# ESP-WROOM32-Breakout_v12.net
KiCad netlist of a schematic drawn in EAGLE
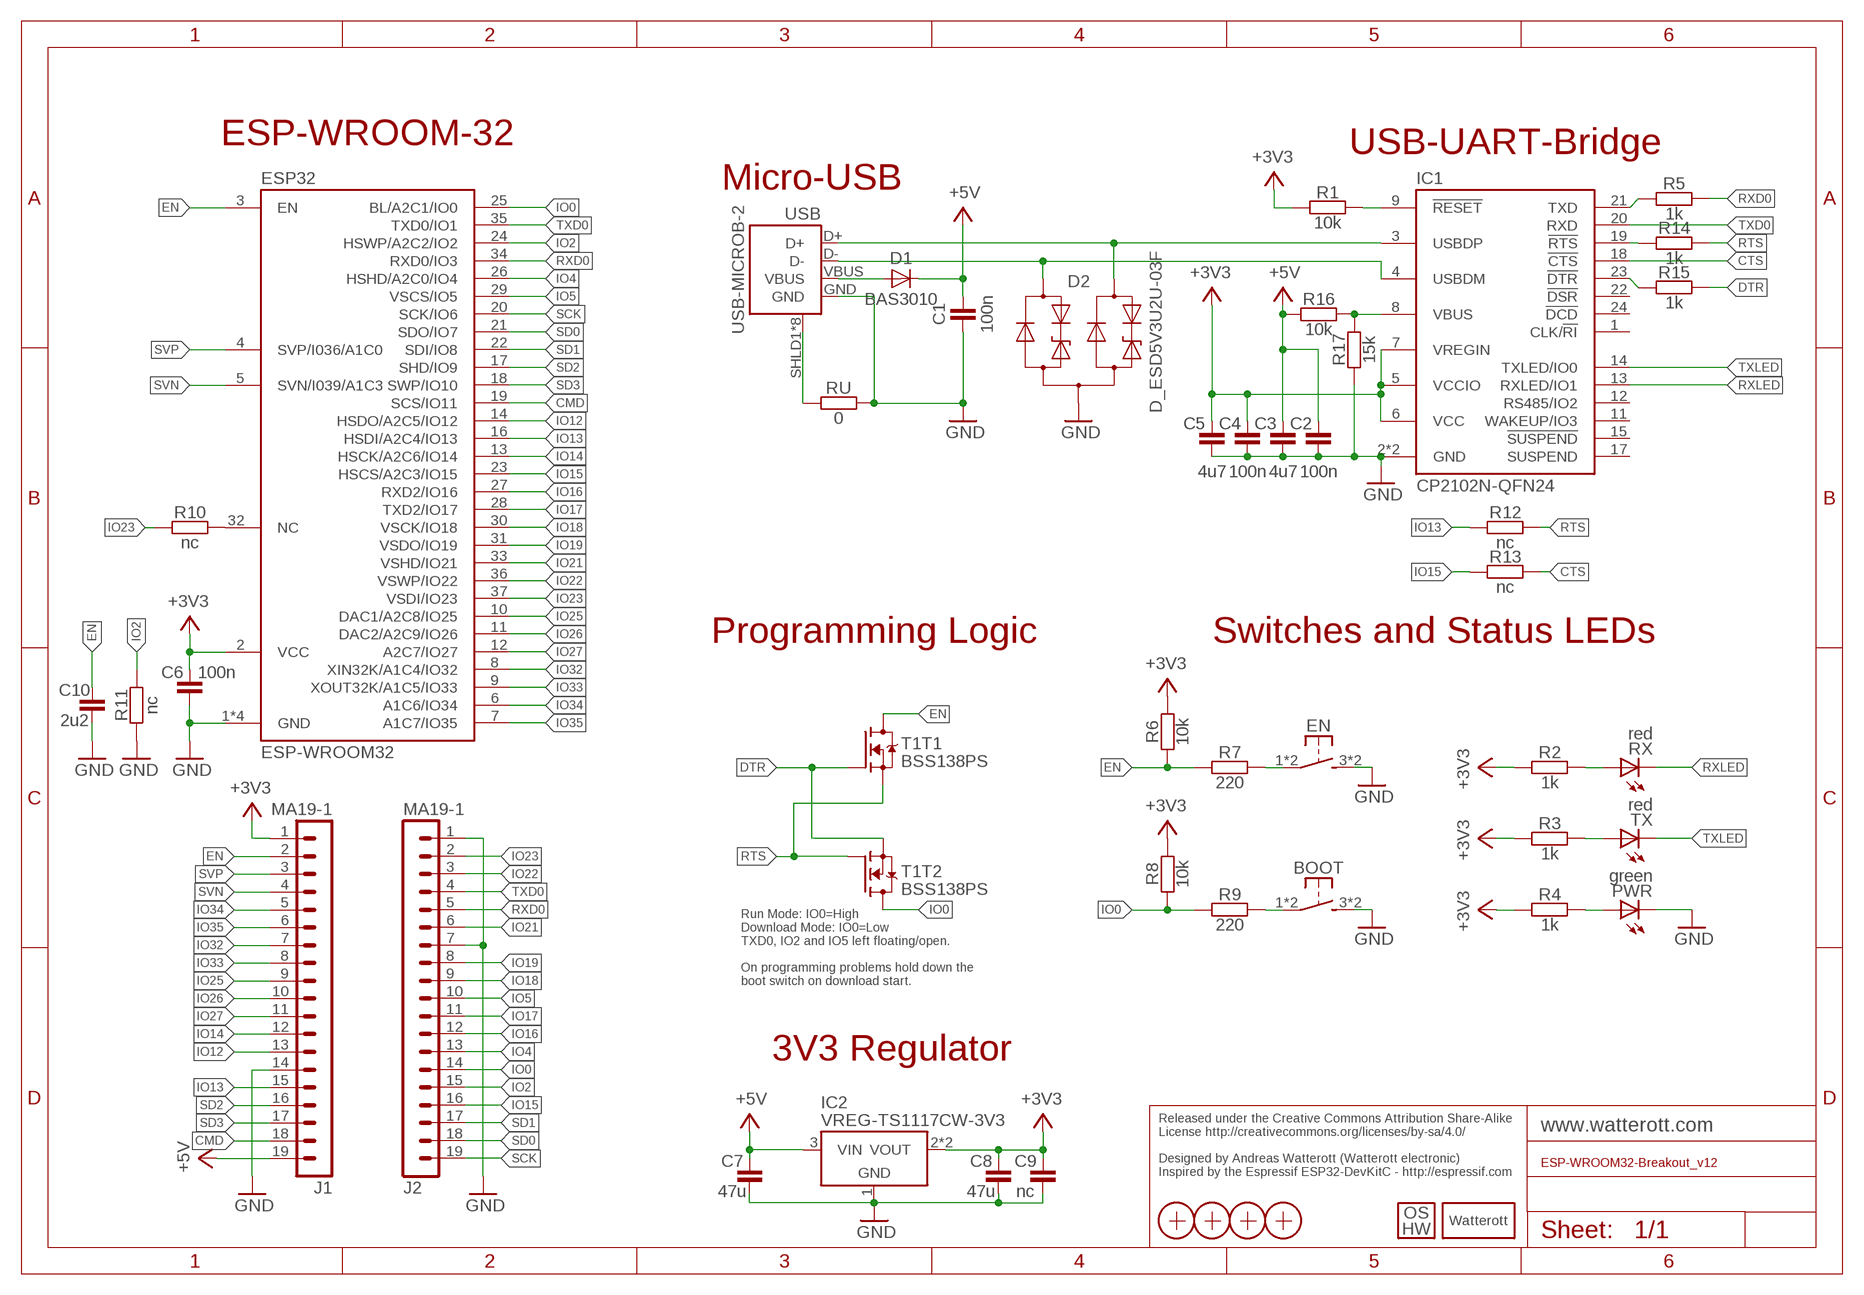
[diagram p0: schematic, sheet 1]

(export (version "E")
  (design (tool "Eeschema 10.0.6"))
  (components
    (comp (ref "BOOT")
      (value "SW-TACTILE-PTS840P")
      (footprint "eagle-import:PTS840P")
      (libsource (lib "eagle-import") (part "SW-TACTILE-PTS840P"))
    )
    (comp (ref "C1")
      (value "100n")
      (footprint "eagle-import:C0402")
      (libsource (lib "eagle-import") (part "CAPACITOR-0402"))
    )
    (comp (ref "C2")
      (value "100n")
      (footprint "eagle-import:C0402")
      (libsource (lib "eagle-import") (part "CAPACITOR-0402"))
    )
    (comp (ref "C3")
      (value "4u7")
      (footprint "eagle-import:C0603")
      (libsource (lib "eagle-import") (part "CAPACITOR-0603"))
    )
    (comp (ref "C4")
      (value "100n")
      (footprint "eagle-import:C0402")
      (libsource (lib "eagle-import") (part "CAPACITOR-0402"))
    )
    (comp (ref "C5")
      (value "4u7")
      (footprint "eagle-import:C0603")
      (libsource (lib "eagle-import") (part "CAPACITOR-0603"))
    )
    (comp (ref "C6")
      (value "100n")
      (footprint "eagle-import:C0402")
      (libsource (lib "eagle-import") (part "CAPACITOR-0402"))
    )
    (comp (ref "C7")
      (value "47u")
      (footprint "eagle-import:C1206")
      (libsource (lib "eagle-import") (part "CAPACITOR-1206"))
    )
    (comp (ref "C8")
      (value "47u")
      (footprint "eagle-import:C1206")
      (libsource (lib "eagle-import") (part "CAPACITOR-1206"))
    )
    (comp (ref "C9")
      (value "nc")
      (footprint "eagle-import:C1206")
      (libsource (lib "eagle-import") (part "CAPACITOR-1206"))
    )
    (comp (ref "C10")
      (value "2u2")
      (footprint "eagle-import:C0402")
      (libsource (lib "eagle-import") (part "CAPACITOR-0402"))
    )
    (comp (ref "D1")
      (value "BAS3010")
      (footprint "eagle-import:SOD323")
      (libsource (lib "eagle-import") (part "DIODE-SOD323"))
    )
    (comp (ref "D2")
      (value "D_ESD5V3U2U-03F")
      (footprint "eagle-import:SOT723")
      (libsource (lib "eagle-import") (part "D_ESD5V3U2U-03F"))
    )
    (comp (ref "EN")
      (value "SW-TACTILE-PTS840P")
      (footprint "eagle-import:PTS840P")
      (libsource (lib "eagle-import") (part "SW-TACTILE-PTS840P"))
    )
    (comp (ref "ESP32")
      (value "ESP-WROOM32")
      (footprint "eagle-import:ESP-WROOM32")
      (libsource (lib "eagle-import") (part "ESP-WROOM32"))
    )
    (comp (ref "IC1")
      (value "CP2102N-QFN24")
      (footprint "eagle-import:QFN24-PAD")
      (libsource (lib "eagle-import") (part "CP2102N-QFN24"))
    )
    (comp (ref "IC2")
      (value "VREG-TS1117CW-3V3")
      (footprint "eagle-import:SOT223")
      (libsource (lib "eagle-import") (part "VREG-TS1117CW-3V3"))
    )
    (comp (ref "J1")
      (value "MA19-1")
      (footprint "eagle-import:MA19-1")
      (libsource (lib "eagle-import") (part "MA19-1"))
    )
    (comp (ref "J2")
      (value "MA19-1")
      (footprint "eagle-import:MA19-1")
      (libsource (lib "eagle-import") (part "MA19-1"))
    )
    (comp (ref "LOGO1")
      (value "LOGO_SPARK-4")
      (footprint "eagle-import:SPARK_4MM")
      (libsource (lib "eagle-import") (part "LOGO_SPARK-4"))
    )
    (comp (ref "LOGO2")
      (value "LOGO_OSHW-2")
      (footprint "eagle-import:OSHW_2MM")
      (libsource (lib "eagle-import") (part "LOGO_OSHW-2"))
    )
    (comp (ref "PWR")
      (value "green")
      (footprint "eagle-import:C0603")
      (libsource (lib "eagle-import") (part "LED-0603"))
    )
    (comp (ref "R1")
      (value "10k")
      (footprint "eagle-import:C0402")
      (libsource (lib "eagle-import") (part "RESISTOR-0402"))
    )
    (comp (ref "R2")
      (value "1k")
      (footprint "eagle-import:C0402")
      (libsource (lib "eagle-import") (part "RESISTOR-0402"))
    )
    (comp (ref "R3")
      (value "1k")
      (footprint "eagle-import:C0402")
      (libsource (lib "eagle-import") (part "RESISTOR-0402"))
    )
    (comp (ref "R4")
      (value "1k")
      (footprint "eagle-import:C0402")
      (libsource (lib "eagle-import") (part "RESISTOR-0402"))
    )
    (comp (ref "R5")
      (value "1k")
      (footprint "eagle-import:C0402")
      (libsource (lib "eagle-import") (part "RESISTOR-0402"))
    )
    (comp (ref "R6")
      (value "10k")
      (footprint "eagle-import:C0402")
      (libsource (lib "eagle-import") (part "RESISTOR-0402"))
    )
    (comp (ref "R7")
      (value "220")
      (footprint "eagle-import:C0402")
      (libsource (lib "eagle-import") (part "RESISTOR-0402"))
    )
    (comp (ref "R8")
      (value "10k")
      (footprint "eagle-import:C0402")
      (libsource (lib "eagle-import") (part "RESISTOR-0402"))
    )
    (comp (ref "R9")
      (value "220")
      (footprint "eagle-import:C0402")
      (libsource (lib "eagle-import") (part "RESISTOR-0402"))
    )
    (comp (ref "R10")
      (value "nc")
      (footprint "eagle-import:C0402")
      (libsource (lib "eagle-import") (part "RESISTOR-0402"))
    )
    (comp (ref "R11")
      (value "nc")
      (footprint "eagle-import:C0402")
      (libsource (lib "eagle-import") (part "RESISTOR-0402"))
    )
    (comp (ref "R12")
      (value "nc")
      (footprint "eagle-import:C0402")
      (libsource (lib "eagle-import") (part "RESISTOR-0402"))
    )
    (comp (ref "R13")
      (value "nc")
      (footprint "eagle-import:C0402")
      (libsource (lib "eagle-import") (part "RESISTOR-0402"))
    )
    (comp (ref "R14")
      (value "1k")
      (footprint "eagle-import:C0402")
      (libsource (lib "eagle-import") (part "RESISTOR-0402"))
    )
    (comp (ref "R15")
      (value "1k")
      (footprint "eagle-import:C0402")
      (libsource (lib "eagle-import") (part "RESISTOR-0402"))
    )
    (comp (ref "R16")
      (value "10k")
      (footprint "eagle-import:C0402")
      (libsource (lib "eagle-import") (part "RESISTOR-0402"))
    )
    (comp (ref "R17")
      (value "15k")
      (footprint "eagle-import:C0402")
      (libsource (lib "eagle-import") (part "RESISTOR-0402"))
    )
    (comp (ref "RU")
      (value "0")
      (footprint "eagle-import:C0402")
      (libsource (lib "eagle-import") (part "RESISTOR-0402"))
    )
    (comp (ref "RX")
      (value "red")
      (footprint "eagle-import:C0603")
      (libsource (lib "eagle-import") (part "LED-0603"))
    )
    (comp (ref "T1")
      (value "BSS138PS")
      (footprint "eagle-import:SOT363")
      (libsource (lib "eagle-import") (part "BSS138PS"))
    )
    (comp (ref "TX")
      (value "red")
      (footprint "eagle-import:C0603")
      (libsource (lib "eagle-import") (part "LED-0603"))
    )
    (comp (ref "USB")
      (value "USB-MICROB-2")
      (footprint "eagle-import:USB-MICROB-10118194")
      (libsource (lib "eagle-import") (part "USB-MICROB-2"))
    )
    (comp (ref "X1")
      (value "PASSER-07")
      (footprint "eagle-import:PASSER_07MM")
      (libsource (lib "eagle-import") (part "PASSER-07"))
    )
    (comp (ref "X2")
      (value "PASSER-07")
      (footprint "eagle-import:PASSER_07MM")
      (libsource (lib "eagle-import") (part "PASSER-07"))
    )
    (comp (ref "X3")
      (value "PASSER-07")
      (footprint "eagle-import:PASSER_07MM")
      (libsource (lib "eagle-import") (part "PASSER-07"))
    )
    (comp (ref "X4")
      (value "PASSER-07")
      (footprint "eagle-import:PASSER_07MM")
      (libsource (lib "eagle-import") (part "PASSER-07"))
    )
  )
  (nets
    (net (code "1") (name "+3V3") (class "Default")
      (node (ref "C4") (pin "2") (pinfunction "2_2") (pintype "passive"))
      (node (ref "C5") (pin "2") (pinfunction "2_2") (pintype "passive"))
      (node (ref "C6") (pin "2") (pinfunction "2_2") (pintype "passive"))
      (node (ref "C8") (pin "2") (pinfunction "2_2") (pintype "passive"))
      (node (ref "C9") (pin "2") (pinfunction "2_2") (pintype "passive"))
      (node (ref "ESP32") (pin "2") (pinfunction "VCC_2") (pintype "power_in"))
      (node (ref "IC1") (pin "5") (pinfunction "VCCIO_5") (pintype "power_in"))
      (node (ref "IC1") (pin "6") (pinfunction "VCC_6") (pintype "power_in"))
      (node (ref "IC1") (pin "7") (pinfunction "VREGIN_7") (pintype "power_in"))
      (node (ref "IC2") (pin "2") (pinfunction "VOUT_2") (pintype "power_in"))
      (node (ref "IC2") (pin "4") (pinfunction "VOUT_4") (pintype "power_in"))
      (node (ref "J1") (pin "1") (pinfunction "1_1") (pintype "passive"))
      (node (ref "R1") (pin "1") (pinfunction "1_1") (pintype "passive"))
      (node (ref "R2") (pin "1") (pinfunction "1_1") (pintype "passive"))
      (node (ref "R3") (pin "1") (pinfunction "1_1") (pintype "passive"))
      (node (ref "R4") (pin "1") (pinfunction "1_1") (pintype "passive"))
      (node (ref "R6") (pin "2") (pinfunction "2_2") (pintype "passive"))
      (node (ref "R8") (pin "2") (pinfunction "2_2") (pintype "passive"))
    )
    (net (code "2") (name "+5V") (class "Default")
      (node (ref "C1") (pin "2") (pinfunction "2_2") (pintype "passive"))
      (node (ref "C2") (pin "2") (pinfunction "2_2") (pintype "passive"))
      (node (ref "C3") (pin "2") (pinfunction "2_2") (pintype "passive"))
      (node (ref "C7") (pin "2") (pinfunction "2_2") (pintype "passive"))
      (node (ref "D1") (pin "C") (pinfunction "C_C") (pintype "passive"))
      (node (ref "IC2") (pin "3") (pinfunction "VIN_3") (pintype "power_in"))
      (node (ref "J1") (pin "19") (pinfunction "19_19") (pintype "passive"))
      (node (ref "R16") (pin "1") (pinfunction "1_1") (pintype "passive"))
    )
    (net (code "3") (name "CMD") (class "Default")
      (node (ref "ESP32") (pin "19") (pinfunction "SCS/IO11_19") (pintype "bidirectional"))
      (node (ref "J1") (pin "18") (pinfunction "18_18") (pintype "passive"))
    )
    (net (code "4") (name "CTS") (class "Default")
      (node (ref "IC1") (pin "18") (pinfunction "~{CTS}_18") (pintype "bidirectional"))
      (node (ref "R13") (pin "2") (pinfunction "2_2") (pintype "passive"))
    )
    (net (code "5") (name "DTR") (class "Default")
      (node (ref "R15") (pin "2") (pinfunction "2_2") (pintype "passive"))
      (node (ref "T1") (pin "2") (pinfunction "G_2") (pintype "passive"))
      (node (ref "T1") (pin "4") (pinfunction "S_4") (pintype "passive"))
    )
    (net (code "6") (name "EN") (class "Default")
      (node (ref "C10") (pin "2") (pinfunction "2_2") (pintype "passive"))
      (node (ref "ESP32") (pin "3") (pinfunction "EN_3") (pintype "bidirectional"))
      (node (ref "J1") (pin "2") (pinfunction "2_2") (pintype "passive"))
      (node (ref "R6") (pin "1") (pinfunction "1_1") (pintype "passive"))
      (node (ref "R7") (pin "1") (pinfunction "1_1") (pintype "passive"))
      (node (ref "T1") (pin "6") (pinfunction "D_6") (pintype "passive"))
    )
    (net (code "7") (name "GND") (class "Default")
      (node (ref "BOOT") (pin "3") (pinfunction "S1_3") (pintype "passive"))
      (node (ref "BOOT") (pin "4") (pinfunction "S1_4") (pintype "passive"))
      (node (ref "C1") (pin "1") (pinfunction "1_1") (pintype "passive"))
      (node (ref "C10") (pin "1") (pinfunction "1_1") (pintype "passive"))
      (node (ref "C2") (pin "1") (pinfunction "1_1") (pintype "passive"))
      (node (ref "C3") (pin "1") (pinfunction "1_1") (pintype "passive"))
      (node (ref "C4") (pin "1") (pinfunction "1_1") (pintype "passive"))
      (node (ref "C5") (pin "1") (pinfunction "1_1") (pintype "passive"))
      (node (ref "C6") (pin "1") (pinfunction "1_1") (pintype "passive"))
      (node (ref "C7") (pin "1") (pinfunction "1_1") (pintype "passive"))
      (node (ref "C8") (pin "1") (pinfunction "1_1") (pintype "passive"))
      (node (ref "C9") (pin "1") (pinfunction "1_1") (pintype "passive"))
      (node (ref "D2") (pin "3") (pinfunction "A_3") (pintype "passive"))
      (node (ref "EN") (pin "3") (pinfunction "S1_3") (pintype "passive"))
      (node (ref "EN") (pin "4") (pinfunction "S1_4") (pintype "passive"))
      (node (ref "ESP32") (pin "1") (pinfunction "GND_1") (pintype "power_in"))
      (node (ref "ESP32") (pin "15") (pinfunction "GND_15") (pintype "power_in"))
      (node (ref "ESP32") (pin "38") (pinfunction "GND_38") (pintype "power_in"))
      (node (ref "ESP32") (pin "TP") (pinfunction "GND_TP") (pintype "power_in"))
      (node (ref "IC1") (pin "2") (pinfunction "GND_2") (pintype "power_in"))
      (node (ref "IC1") (pin "TP") (pinfunction "GND_TP") (pintype "power_in"))
      (node (ref "IC2") (pin "1") (pinfunction "GND_1") (pintype "power_in"))
      (node (ref "J1") (pin "14") (pinfunction "14_14") (pintype "passive"))
      (node (ref "J2") (pin "1") (pinfunction "1_1") (pintype "passive"))
      (node (ref "J2") (pin "7") (pinfunction "7_7") (pintype "passive"))
      (node (ref "PWR") (pin "C") (pinfunction "C_C") (pintype "passive"))
      (node (ref "R11") (pin "1") (pinfunction "1_1") (pintype "passive"))
      (node (ref "R17") (pin "1") (pinfunction "1_1") (pintype "passive"))
      (node (ref "RU") (pin "2") (pinfunction "2_2") (pintype "passive"))
      (node (ref "USB") (pin "GND") (pinfunction "GND_GND") (pintype "power_in"))
    )
    (net (code "8") (name "IO0") (class "Default")
      (node (ref "ESP32") (pin "25") (pinfunction "BL/A2C1/IO0_25") (pintype "bidirectional"))
      (node (ref "J2") (pin "14") (pinfunction "14_14") (pintype "passive"))
      (node (ref "R8") (pin "1") (pinfunction "1_1") (pintype "passive"))
      (node (ref "R9") (pin "1") (pinfunction "1_1") (pintype "passive"))
      (node (ref "T1") (pin "3") (pinfunction "D_3") (pintype "passive"))
    )
    (net (code "9") (name "IO2") (class "Default")
      (node (ref "ESP32") (pin "24") (pinfunction "HSWP/A2C2/IO2_24") (pintype "bidirectional"))
      (node (ref "J2") (pin "15") (pinfunction "15_15") (pintype "passive"))
      (node (ref "R11") (pin "2") (pinfunction "2_2") (pintype "passive"))
    )
    (net (code "10") (name "IO4") (class "Default")
      (node (ref "ESP32") (pin "26") (pinfunction "HSHD/A2C0/IO4_26") (pintype "bidirectional"))
      (node (ref "J2") (pin "13") (pinfunction "13_13") (pintype "passive"))
    )
    (net (code "11") (name "IO5") (class "Default")
      (node (ref "ESP32") (pin "29") (pinfunction "VSCS/IO5_29") (pintype "bidirectional"))
      (node (ref "J2") (pin "10") (pinfunction "10_10") (pintype "passive"))
    )
    (net (code "12") (name "IO12") (class "Default")
      (node (ref "ESP32") (pin "14") (pinfunction "HSDO/A2C5/IO12_14") (pintype "bidirectional"))
      (node (ref "J1") (pin "13") (pinfunction "13_13") (pintype "passive"))
    )
    (net (code "13") (name "IO13") (class "Default")
      (node (ref "ESP32") (pin "16") (pinfunction "HSDI/A2C4/IO13_16") (pintype "bidirectional"))
      (node (ref "J1") (pin "15") (pinfunction "15_15") (pintype "passive"))
      (node (ref "R12") (pin "1") (pinfunction "1_1") (pintype "passive"))
    )
    (net (code "14") (name "IO14") (class "Default")
      (node (ref "ESP32") (pin "13") (pinfunction "HSCK/A2C6/IO14_13") (pintype "bidirectional"))
      (node (ref "J1") (pin "12") (pinfunction "12_12") (pintype "passive"))
    )
    (net (code "15") (name "IO15") (class "Default")
      (node (ref "ESP32") (pin "23") (pinfunction "HSCS/A2C3/IO15_23") (pintype "bidirectional"))
      (node (ref "J2") (pin "16") (pinfunction "16_16") (pintype "passive"))
      (node (ref "R13") (pin "1") (pinfunction "1_1") (pintype "passive"))
    )
    (net (code "16") (name "IO16") (class "Default")
      (node (ref "ESP32") (pin "27") (pinfunction "RXD2/IO16_27") (pintype "bidirectional"))
      (node (ref "J2") (pin "12") (pinfunction "12_12") (pintype "passive"))
    )
    (net (code "17") (name "IO17") (class "Default")
      (node (ref "ESP32") (pin "28") (pinfunction "TXD2/IO17_28") (pintype "bidirectional"))
      (node (ref "J2") (pin "11") (pinfunction "11_11") (pintype "passive"))
    )
    (net (code "18") (name "IO18") (class "Default")
      (node (ref "ESP32") (pin "30") (pinfunction "VSCK/IO18_30") (pintype "bidirectional"))
      (node (ref "J2") (pin "9") (pinfunction "9_9") (pintype "passive"))
    )
    (net (code "19") (name "IO19") (class "Default")
      (node (ref "ESP32") (pin "31") (pinfunction "VSDO/IO19_31") (pintype "bidirectional"))
      (node (ref "J2") (pin "8") (pinfunction "8_8") (pintype "passive"))
    )
    (net (code "20") (name "IO21") (class "Default")
      (node (ref "ESP32") (pin "33") (pinfunction "VSHD/IO21_33") (pintype "bidirectional"))
      (node (ref "J2") (pin "6") (pinfunction "6_6") (pintype "passive"))
    )
    (net (code "21") (name "IO22") (class "Default")
      (node (ref "ESP32") (pin "36") (pinfunction "VSWP/IO22_36") (pintype "bidirectional"))
      (node (ref "J2") (pin "3") (pinfunction "3_3") (pintype "passive"))
    )
    (net (code "22") (name "IO23") (class "Default")
      (node (ref "ESP32") (pin "37") (pinfunction "VSDI/IO23_37") (pintype "bidirectional"))
      (node (ref "J2") (pin "2") (pinfunction "2_2") (pintype "passive"))
      (node (ref "R10") (pin "1") (pinfunction "1_1") (pintype "passive"))
    )
    (net (code "23") (name "IO25") (class "Default")
      (node (ref "ESP32") (pin "10") (pinfunction "DAC1/A2C8/IO25_10") (pintype "bidirectional"))
      (node (ref "J1") (pin "9") (pinfunction "9_9") (pintype "passive"))
    )
    (net (code "24") (name "IO26") (class "Default")
      (node (ref "ESP32") (pin "11") (pinfunction "DAC2/A2C9/IO26_11") (pintype "bidirectional"))
      (node (ref "J1") (pin "10") (pinfunction "10_10") (pintype "passive"))
    )
    (net (code "25") (name "IO27") (class "Default")
      (node (ref "ESP32") (pin "12") (pinfunction "A2C7/IO27_12") (pintype "bidirectional"))
      (node (ref "J1") (pin "11") (pinfunction "11_11") (pintype "passive"))
    )
    (net (code "26") (name "IO32") (class "Default")
      (node (ref "ESP32") (pin "8") (pinfunction "XIN32K/A1C4/IO32_8") (pintype "bidirectional"))
      (node (ref "J1") (pin "7") (pinfunction "7_7") (pintype "passive"))
    )
    (net (code "27") (name "IO33") (class "Default")
      (node (ref "ESP32") (pin "9") (pinfunction "XOUT32K/A1C5/IO33_9") (pintype "bidirectional"))
      (node (ref "J1") (pin "8") (pinfunction "8_8") (pintype "passive"))
    )
    (net (code "28") (name "IO34") (class "Default")
      (node (ref "ESP32") (pin "6") (pinfunction "A1C6/IO34_6") (pintype "bidirectional"))
      (node (ref "J1") (pin "5") (pinfunction "5_5") (pintype "passive"))
    )
    (net (code "29") (name "IO35") (class "Default")
      (node (ref "ESP32") (pin "7") (pinfunction "A1C7/IO35_7") (pintype "bidirectional"))
      (node (ref "J1") (pin "6") (pinfunction "6_6") (pintype "passive"))
    )
    (net (code "30") (name "Net-(BOOT-P1-Pad1)") (class "Default")
      (node (ref "BOOT") (pin "1") (pinfunction "P1_1") (pintype "passive"))
      (node (ref "BOOT") (pin "2") (pinfunction "P1_2") (pintype "passive"))
      (node (ref "R9") (pin "2") (pinfunction "2_2") (pintype "passive"))
    )
    (net (code "31") (name "Net-(D1-PadA)") (class "Default")
      (node (ref "D1") (pin "A") (pinfunction "A_A") (pintype "passive"))
      (node (ref "USB") (pin "VBUS") (pinfunction "VBUS_VBUS") (pintype "power_in"))
    )
    (net (code "32") (name "Net-(D2-C1)") (class "Default")
      (node (ref "D2") (pin "1") (pinfunction "C1_1") (pintype "passive"))
      (node (ref "IC1") (pin "4") (pinfunction "USBDM_4") (pintype "bidirectional"))
      (node (ref "USB") (pin "D-") (pinfunction "D-_D-") (pintype "bidirectional"))
    )
    (net (code "33") (name "Net-(D2-C2)") (class "Default")
      (node (ref "D2") (pin "2") (pinfunction "C2_2") (pintype "passive"))
      (node (ref "IC1") (pin "3") (pinfunction "USBDP_3") (pintype "bidirectional"))
      (node (ref "USB") (pin "D+") (pinfunction "D+_D+") (pintype "bidirectional"))
    )
    (net (code "34") (name "Net-(EN-P1-Pad1)") (class "Default")
      (node (ref "EN") (pin "1") (pinfunction "P1_1") (pintype "passive"))
      (node (ref "EN") (pin "2") (pinfunction "P1_2") (pintype "passive"))
      (node (ref "R7") (pin "2") (pinfunction "2_2") (pintype "passive"))
    )
    (net (code "35") (name "Net-(ESP32-NC)") (class "Default")
      (node (ref "ESP32") (pin "32") (pinfunction "NC_32") (pintype "bidirectional"))
      (node (ref "R10") (pin "2") (pinfunction "2_2") (pintype "passive"))
    )
    (net (code "36") (name "Net-(IC1-TXD)") (class "Default")
      (node (ref "IC1") (pin "21") (pinfunction "TXD_21") (pintype "bidirectional"))
      (node (ref "R5") (pin "1") (pinfunction "1_1") (pintype "passive"))
    )
    (net (code "37") (name "Net-(IC1-VBUS)") (class "Default")
      (node (ref "IC1") (pin "8") (pinfunction "VBUS_8") (pintype "power_in"))
      (node (ref "R16") (pin "2") (pinfunction "2_2") (pintype "passive"))
      (node (ref "R17") (pin "2") (pinfunction "2_2") (pintype "passive"))
    )
    (net (code "38") (name "Net-(IC1-~{DTR})") (class "Default")
      (node (ref "IC1") (pin "23") (pinfunction "~{DTR}_23") (pintype "bidirectional"))
      (node (ref "R15") (pin "1") (pinfunction "1_1") (pintype "passive"))
    )
    (net (code "39") (name "Net-(IC1-~{RESET})") (class "Default")
      (node (ref "IC1") (pin "9") (pinfunction "~{RESET}_9") (pintype "bidirectional"))
      (node (ref "R1") (pin "2") (pinfunction "2_2") (pintype "passive"))
    )
    (net (code "40") (name "Net-(IC1-~{RTS})") (class "Default")
      (node (ref "IC1") (pin "19") (pinfunction "~{RTS}_19") (pintype "bidirectional"))
      (node (ref "R14") (pin "1") (pinfunction "1_1") (pintype "passive"))
    )
    (net (code "41") (name "Net-(PWR-PadA)") (class "Default")
      (node (ref "PWR") (pin "A") (pinfunction "A_A") (pintype "passive"))
      (node (ref "R4") (pin "2") (pinfunction "2_2") (pintype "passive"))
    )
    (net (code "42") (name "Net-(R2-Pad2)") (class "Default")
      (node (ref "R2") (pin "2") (pinfunction "2_2") (pintype "passive"))
      (node (ref "RX") (pin "A") (pinfunction "A_A") (pintype "passive"))
    )
    (net (code "43") (name "Net-(R3-Pad2)") (class "Default")
      (node (ref "R3") (pin "2") (pinfunction "2_2") (pintype "passive"))
      (node (ref "TX") (pin "A") (pinfunction "A_A") (pintype "passive"))
    )
    (net (code "44") (name "Net-(RU-Pad1)") (class "Default")
      (node (ref "RU") (pin "1") (pinfunction "1_1") (pintype "passive"))
      (node (ref "USB") (pin "SHLD1") (pinfunction "SHIELD_SHLD1") (pintype "passive"))
      (node (ref "USB") (pin "SHLD2") (pinfunction "SHIELD_SHLD2") (pintype "passive"))
      (node (ref "USB") (pin "SHLD3") (pinfunction "SHIELD_SHLD3") (pintype "passive"))
      (node (ref "USB") (pin "SHLD4") (pinfunction "SHIELD_SHLD4") (pintype "passive"))
      (node (ref "USB") (pin "SHLD5") (pinfunction "SHIELD_SHLD5") (pintype "passive"))
      (node (ref "USB") (pin "SHLD6") (pinfunction "SHIELD_SHLD6") (pintype "passive"))
      (node (ref "USB") (pin "SHLD7") (pinfunction "SHIELD_SHLD7") (pintype "passive"))
      (node (ref "USB") (pin "SHLD8") (pinfunction "SHIELD_SHLD8") (pintype "passive"))
    )
    (net (code "45") (name "RTS") (class "Default")
      (node (ref "R12") (pin "2") (pinfunction "2_2") (pintype "passive"))
      (node (ref "R14") (pin "2") (pinfunction "2_2") (pintype "passive"))
      (node (ref "T1") (pin "1") (pinfunction "S_1") (pintype "passive"))
      (node (ref "T1") (pin "5") (pinfunction "G_5") (pintype "passive"))
    )
    (net (code "46") (name "RXD0") (class "Default")
      (node (ref "ESP32") (pin "34") (pinfunction "RXD0/IO3_34") (pintype "bidirectional"))
      (node (ref "J2") (pin "5") (pinfunction "5_5") (pintype "passive"))
      (node (ref "R5") (pin "2") (pinfunction "2_2") (pintype "passive"))
    )
    (net (code "47") (name "RXLED") (class "Default")
      (node (ref "IC1") (pin "13") (pinfunction "RXLED/IO1_13") (pintype "bidirectional"))
      (node (ref "RX") (pin "C") (pinfunction "C_C") (pintype "passive"))
    )
    (net (code "48") (name "SCK") (class "Default")
      (node (ref "ESP32") (pin "20") (pinfunction "SCK/IO6_20") (pintype "bidirectional"))
      (node (ref "J2") (pin "19") (pinfunction "19_19") (pintype "passive"))
    )
    (net (code "49") (name "SD0") (class "Default")
      (node (ref "ESP32") (pin "21") (pinfunction "SDO/IO7_21") (pintype "bidirectional"))
      (node (ref "J2") (pin "18") (pinfunction "18_18") (pintype "passive"))
    )
    (net (code "50") (name "SD1") (class "Default")
      (node (ref "ESP32") (pin "22") (pinfunction "SDI/IO8_22") (pintype "bidirectional"))
      (node (ref "J2") (pin "17") (pinfunction "17_17") (pintype "passive"))
    )
    (net (code "51") (name "SD2") (class "Default")
      (node (ref "ESP32") (pin "17") (pinfunction "SHD/IO9_17") (pintype "bidirectional"))
      (node (ref "J1") (pin "16") (pinfunction "16_16") (pintype "passive"))
    )
    (net (code "52") (name "SD3") (class "Default")
      (node (ref "ESP32") (pin "18") (pinfunction "SWP/IO10_18") (pintype "bidirectional"))
      (node (ref "J1") (pin "17") (pinfunction "17_17") (pintype "passive"))
    )
    (net (code "53") (name "SVN") (class "Default")
      (node (ref "ESP32") (pin "5") (pinfunction "SVN/I039/A1C3_5") (pintype "bidirectional"))
      (node (ref "J1") (pin "4") (pinfunction "4_4") (pintype "passive"))
    )
    (net (code "54") (name "SVP") (class "Default")
      (node (ref "ESP32") (pin "4") (pinfunction "SVP/I036/A1C0_4") (pintype "bidirectional"))
      (node (ref "J1") (pin "3") (pinfunction "3_3") (pintype "passive"))
    )
    (net (code "55") (name "TXD0") (class "Default")
      (node (ref "ESP32") (pin "35") (pinfunction "TXD0/IO1_35") (pintype "bidirectional"))
      (node (ref "IC1") (pin "20") (pinfunction "RXD_20") (pintype "bidirectional"))
      (node (ref "J2") (pin "4") (pinfunction "4_4") (pintype "passive"))
    )
    (net (code "56") (name "TXLED") (class "Default")
      (node (ref "IC1") (pin "14") (pinfunction "TXLED/IO0_14") (pintype "bidirectional"))
      (node (ref "TX") (pin "C") (pinfunction "C_C") (pintype "passive"))
    )
    (net (code "57") (name "unconnected-(IC1-CLK{slash}~{RI}-Pad1)") (class "Default")
      (node (ref "IC1") (pin "1") (pinfunction "CLK/~{RI}_1") (pintype "bidirectional"))
    )
    (net (code "58") (name "unconnected-(IC1-RS485{slash}IO2-Pad12)") (class "Default")
      (node (ref "IC1") (pin "12") (pinfunction "RS485/IO2_12") (pintype "bidirectional"))
    )
    (net (code "59") (name "unconnected-(IC1-SUSPEND-Pad17)") (class "Default")
      (node (ref "IC1") (pin "17") (pinfunction "SUSPEND_17") (pintype "bidirectional"))
    )
    (net (code "60") (name "unconnected-(IC1-WAKEUP{slash}IO3-Pad11)") (class "Default")
      (node (ref "IC1") (pin "11") (pinfunction "WAKEUP/IO3_11") (pintype "bidirectional"))
    )
    (net (code "61") (name "unconnected-(IC1-~{DCD}-Pad24)") (class "Default")
      (node (ref "IC1") (pin "24") (pinfunction "~{DCD}_24") (pintype "bidirectional"))
    )
    (net (code "62") (name "unconnected-(IC1-~{DSR}-Pad22)") (class "Default")
      (node (ref "IC1") (pin "22") (pinfunction "~{DSR}_22") (pintype "bidirectional"))
    )
    (net (code "63") (name "unconnected-(IC1-~{SUSPEND}-Pad15)") (class "Default")
      (node (ref "IC1") (pin "15") (pinfunction "~{SUSPEND}_15") (pintype "bidirectional"))
    )
  )
)
